# badge_buttons.net
KiCad netlist of a schematic drawn in EAGLE
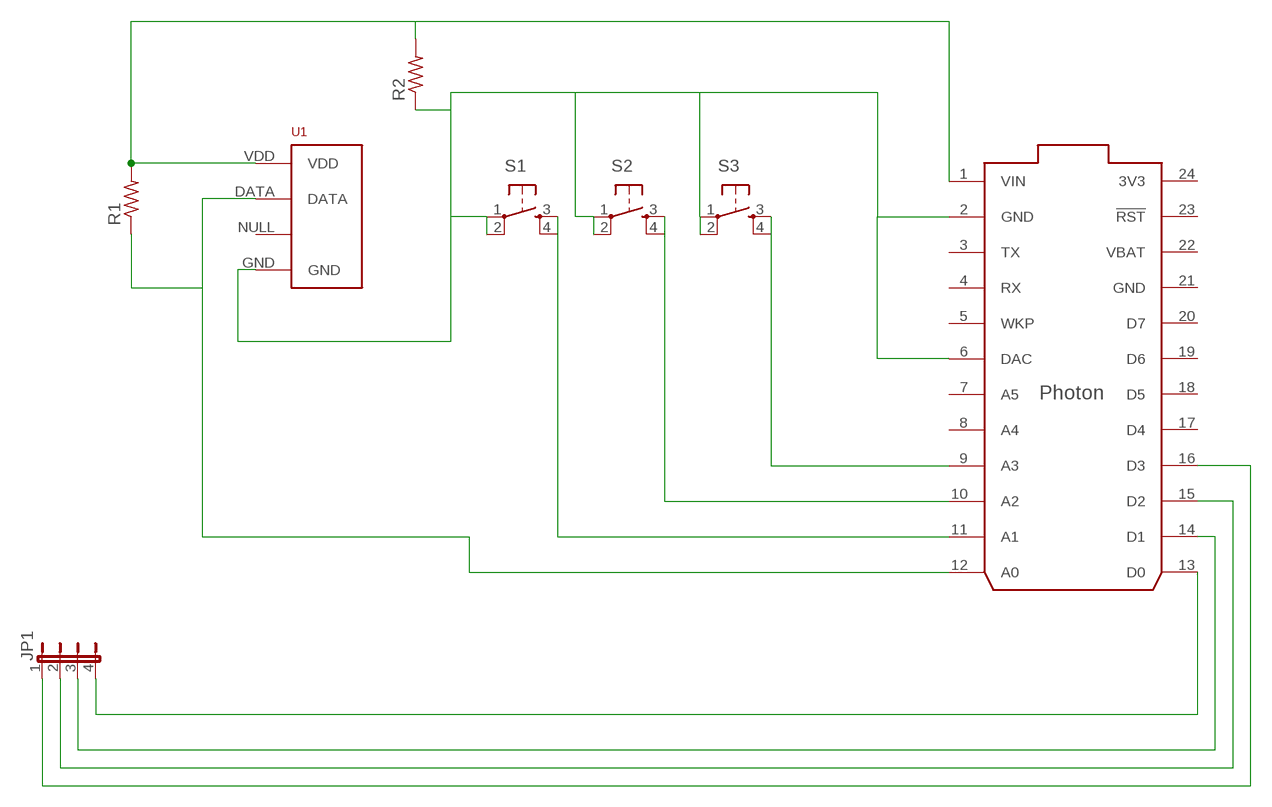
[diagram p0: schematic, sheet 1]

(export (version "E")
  (design (tool "Eeschema 10.0.6"))
  (components
    (comp (ref "JP1")
      (value "JP4E")
      (footprint "eagle-import:JP4")
      (libsource (lib "eagle-import") (part "JP4E"))
    )
    (comp (ref "R1")
      (value "R-US_0204/7")
      (footprint "eagle-import:0204_7")
      (libsource (lib "eagle-import") (part "R-US_0204/7"))
    )
    (comp (ref "R2")
      (value "R-US_0204/7")
      (footprint "eagle-import:0204_7")
      (libsource (lib "eagle-import") (part "R-US_0204/7"))
    )
    (comp (ref "S1")
      (value "TAC_SWITCHPTH")
      (footprint "eagle-import:TACTILE-PTH")
      (libsource (lib "eagle-import") (part "TAC_SWITCHPTH"))
    )
    (comp (ref "S2")
      (value "TAC_SWITCHPTH")
      (footprint "eagle-import:TACTILE-PTH")
      (libsource (lib "eagle-import") (part "TAC_SWITCHPTH"))
    )
    (comp (ref "S3")
      (value "TAC_SWITCHPTH")
      (footprint "eagle-import:TACTILE-PTH")
      (libsource (lib "eagle-import") (part "TAC_SWITCHPTH"))
    )
    (comp (ref "U$1")
      (value "PHOTON_WITH_HEADERS")
      (footprint "eagle-import:PHOTON")
      (libsource (lib "eagle-import") (part "PHOTON_WITH_HEADERS"))
    )
    (comp (ref "U1")
      (value "RHT03_DHT-22_AM2302")
      (footprint "eagle-import:RHT03_DHT-22")
      (libsource (lib "eagle-import") (part "RHT03_DHT-22_AM2302"))
    )
  )
  (nets
    (net (code "1") (name "/3V3") (class "Default")
      (node (ref "U$1") (pin "24") (pinfunction "3V3_24") (pintype "power_in"))
    )
    (net (code "2") (name "/GND") (class "Default")
      (node (ref "U$1") (pin "21") (pinfunction "GND_21") (pintype "power_in"))
    )
    (net (code "3") (name "/VBAT") (class "Default")
      (node (ref "U$1") (pin "22") (pinfunction "VBAT_22") (pintype "power_in"))
    )
    (net (code "4") (name "Net-(U$1-A0)") (class "Default")
      (node (ref "R1") (pin "1") (pinfunction "1_1") (pintype "passive"))
      (node (ref "U$1") (pin "12") (pinfunction "A0_12") (pintype "bidirectional"))
      (node (ref "U1") (pin "DATA") (pinfunction "DATA_DATA") (pintype "bidirectional"))
    )
    (net (code "5") (name "Net-(U$1-A1)") (class "Default")
      (node (ref "S1") (pin "3") (pinfunction "3_3") (pintype "passive"))
      (node (ref "S1") (pin "4") (pinfunction "4_4") (pintype "passive"))
      (node (ref "U$1") (pin "11") (pinfunction "A1_11") (pintype "bidirectional"))
    )
    (net (code "6") (name "Net-(U$1-A2)") (class "Default")
      (node (ref "S2") (pin "3") (pinfunction "3_3") (pintype "passive"))
      (node (ref "S2") (pin "4") (pinfunction "4_4") (pintype "passive"))
      (node (ref "U$1") (pin "10") (pinfunction "A2_10") (pintype "bidirectional"))
    )
    (net (code "7") (name "Net-(U$1-A3)") (class "Default")
      (node (ref "S3") (pin "3") (pinfunction "3_3") (pintype "passive"))
      (node (ref "S3") (pin "4") (pinfunction "4_4") (pintype "passive"))
      (node (ref "U$1") (pin "9") (pinfunction "A3_9") (pintype "bidirectional"))
    )
    (net (code "8") (name "Net-(U$1-D0)") (class "Default")
      (node (ref "JP1") (pin "4") (pinfunction "4_4") (pintype "passive"))
      (node (ref "U$1") (pin "13") (pinfunction "D0_13") (pintype "bidirectional"))
    )
    (net (code "9") (name "Net-(U$1-D1)") (class "Default")
      (node (ref "JP1") (pin "3") (pinfunction "3_3") (pintype "passive"))
      (node (ref "U$1") (pin "14") (pinfunction "D1_14") (pintype "bidirectional"))
    )
    (net (code "10") (name "Net-(U$1-D2)") (class "Default")
      (node (ref "JP1") (pin "2") (pinfunction "2_2") (pintype "passive"))
      (node (ref "U$1") (pin "15") (pinfunction "D2_15") (pintype "bidirectional"))
    )
    (net (code "11") (name "Net-(U$1-D3)") (class "Default")
      (node (ref "JP1") (pin "1") (pinfunction "1_1") (pintype "passive"))
      (node (ref "U$1") (pin "16") (pinfunction "D3_16") (pintype "bidirectional"))
    )
    (net (code "12") (name "Net-(U$1-DAC)") (class "Default")
      (node (ref "R2") (pin "1") (pinfunction "1_1") (pintype "passive"))
      (node (ref "S1") (pin "1") (pinfunction "1_1") (pintype "passive"))
      (node (ref "S1") (pin "2") (pinfunction "2_2") (pintype "passive"))
      (node (ref "S2") (pin "1") (pinfunction "1_1") (pintype "passive"))
      (node (ref "S2") (pin "2") (pinfunction "2_2") (pintype "passive"))
      (node (ref "S3") (pin "1") (pinfunction "1_1") (pintype "passive"))
      (node (ref "S3") (pin "2") (pinfunction "2_2") (pintype "passive"))
      (node (ref "U$1") (pin "2") (pinfunction "GND_2") (pintype "power_in"))
      (node (ref "U$1") (pin "6") (pinfunction "DAC_6") (pintype "bidirectional"))
      (node (ref "U1") (pin "GND") (pinfunction "GND_GND") (pintype "power_in"))
    )
    (net (code "13") (name "Net-(U$1-VIN)") (class "Default")
      (node (ref "R1") (pin "2") (pinfunction "2_2") (pintype "passive"))
      (node (ref "R2") (pin "2") (pinfunction "2_2") (pintype "passive"))
      (node (ref "U$1") (pin "1") (pinfunction "VIN_1") (pintype "power_in"))
      (node (ref "U1") (pin "VDD") (pinfunction "VDD_VDD") (pintype "power_in"))
    )
    (net (code "14") (name "unconnected-(U$1-A4-Pad8)") (class "Default")
      (node (ref "U$1") (pin "8") (pinfunction "A4_8") (pintype "bidirectional"))
    )
    (net (code "15") (name "unconnected-(U$1-A5-Pad7)") (class "Default")
      (node (ref "U$1") (pin "7") (pinfunction "A5_7") (pintype "bidirectional"))
    )
    (net (code "16") (name "unconnected-(U$1-D4-Pad17)") (class "Default")
      (node (ref "U$1") (pin "17") (pinfunction "D4_17") (pintype "bidirectional"))
    )
    (net (code "17") (name "unconnected-(U$1-D5-Pad18)") (class "Default")
      (node (ref "U$1") (pin "18") (pinfunction "D5_18") (pintype "bidirectional"))
    )
    (net (code "18") (name "unconnected-(U$1-D6-Pad19)") (class "Default")
      (node (ref "U$1") (pin "19") (pinfunction "D6_19") (pintype "bidirectional"))
    )
    (net (code "19") (name "unconnected-(U$1-D7-Pad20)") (class "Default")
      (node (ref "U$1") (pin "20") (pinfunction "D7_20") (pintype "bidirectional"))
    )
    (net (code "20") (name "unconnected-(U$1-RX-Pad4)") (class "Default")
      (node (ref "U$1") (pin "4") (pinfunction "RX_4") (pintype "bidirectional"))
    )
    (net (code "21") (name "unconnected-(U$1-TX-Pad3)") (class "Default")
      (node (ref "U$1") (pin "3") (pinfunction "TX_3") (pintype "bidirectional"))
    )
    (net (code "22") (name "unconnected-(U$1-WKP-Pad5)") (class "Default")
      (node (ref "U$1") (pin "5") (pinfunction "WKP_5") (pintype "bidirectional"))
    )
    (net (code "23") (name "unconnected-(U$1-~{RST}-Pad23)") (class "Default")
      (node (ref "U$1") (pin "23") (pinfunction "~{RST}_23") (pintype "bidirectional"))
    )
    (net (code "24") (name "unconnected-(U1-PadNULL)") (class "Default")
      (node (ref "U1") (pin "NULL") (pinfunction "NULL_NULL") (pintype "no_connect"))
    )
  )
)
